# Boobie_LS2074M2G.net
KiCad netlist of a schematic drawn in EAGLE
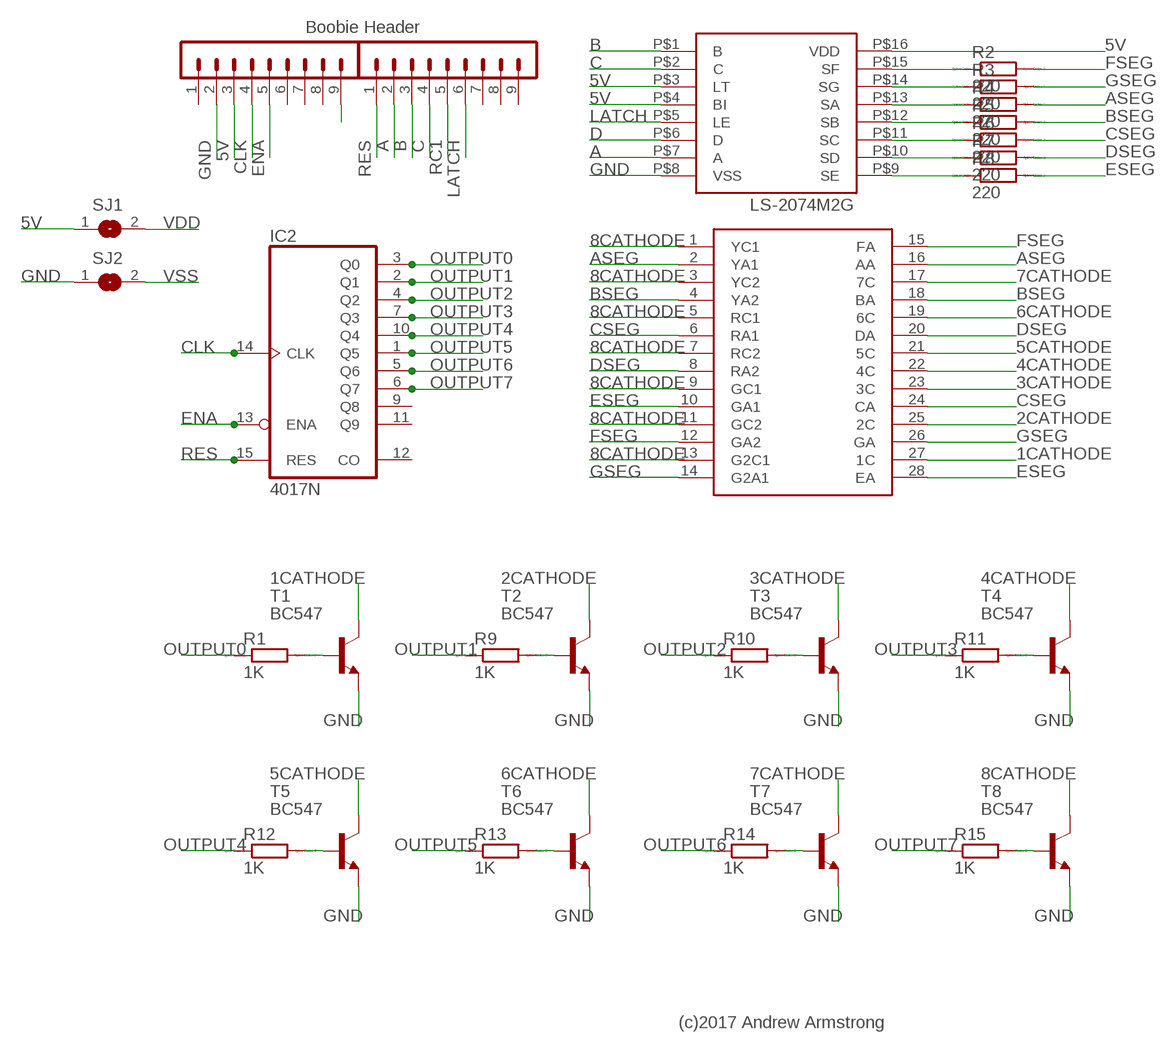
[diagram p0: schematic, sheet 1]

(export (version "E")
  (design (tool "Eeschema 10.0.6"))
  (components
    (comp (ref "IC2")
      (value "4017N")
      (footprint "eagle-import:DIL16")
      (libsource (lib "eagle-import") (part "4017N"))
    )
    (comp (ref "R1")
      (value "1K")
      (footprint "eagle-import:0204_7")
      (libsource (lib "eagle-import") (part "R0204/7"))
    )
    (comp (ref "R2")
      (value "220")
      (footprint "eagle-import:0204_7")
      (libsource (lib "eagle-import") (part "R0204/7"))
    )
    (comp (ref "R3")
      (value "220")
      (footprint "eagle-import:0204_7")
      (libsource (lib "eagle-import") (part "R0204/7"))
    )
    (comp (ref "R4")
      (value "220")
      (footprint "eagle-import:0204_7")
      (libsource (lib "eagle-import") (part "R0204/7"))
    )
    (comp (ref "R5")
      (value "220")
      (footprint "eagle-import:0204_7")
      (libsource (lib "eagle-import") (part "R0204/7"))
    )
    (comp (ref "R6")
      (value "220")
      (footprint "eagle-import:0204_7")
      (libsource (lib "eagle-import") (part "R0204/7"))
    )
    (comp (ref "R7")
      (value "220")
      (footprint "eagle-import:0204_7")
      (libsource (lib "eagle-import") (part "R0204/7"))
    )
    (comp (ref "R8")
      (value "220")
      (footprint "eagle-import:0204_7")
      (libsource (lib "eagle-import") (part "R0204/7"))
    )
    (comp (ref "R9")
      (value "1K")
      (footprint "eagle-import:0204_7")
      (libsource (lib "eagle-import") (part "R0204/7"))
    )
    (comp (ref "R10")
      (value "1K")
      (footprint "eagle-import:0204_7")
      (libsource (lib "eagle-import") (part "R0204/7"))
    )
    (comp (ref "R11")
      (value "1K")
      (footprint "eagle-import:0204_7")
      (libsource (lib "eagle-import") (part "R0204/7"))
    )
    (comp (ref "R12")
      (value "1K")
      (footprint "eagle-import:0204_7")
      (libsource (lib "eagle-import") (part "R0204/7"))
    )
    (comp (ref "R13")
      (value "1K")
      (footprint "eagle-import:0204_7")
      (libsource (lib "eagle-import") (part "R0204/7"))
    )
    (comp (ref "R14")
      (value "1K")
      (footprint "eagle-import:0204_7")
      (libsource (lib "eagle-import") (part "R0204/7"))
    )
    (comp (ref "R15")
      (value "1K")
      (footprint "eagle-import:0204_7")
      (libsource (lib "eagle-import") (part "R0204/7"))
    )
    (comp (ref "SJ1") (value "SJ") (footprint "eagle-import:SJ") (libsource (lib "eagle-import") (part "SJ")))
    (comp (ref "SJ2") (value "SJ") (footprint "eagle-import:SJ") (libsource (lib "eagle-import") (part "SJ")))
    (comp (ref "SV1")
      (value "MA09-1")
      (footprint "eagle-import:MA09-1")
      (libsource (lib "eagle-import") (part "MA09-1"))
    )
    (comp (ref "SV2")
      (value "MA09-1")
      (footprint "eagle-import:MA09-1")
      (libsource (lib "eagle-import") (part "MA09-1"))
    )
    (comp (ref "T1")
      (value "BC547")
      (footprint "eagle-import:TO92")
      (libsource (lib "eagle-import") (part "BC547"))
    )
    (comp (ref "T2")
      (value "BC547")
      (footprint "eagle-import:TO92")
      (libsource (lib "eagle-import") (part "BC547"))
    )
    (comp (ref "T3")
      (value "BC547")
      (footprint "eagle-import:TO92")
      (libsource (lib "eagle-import") (part "BC547"))
    )
    (comp (ref "T4")
      (value "BC547")
      (footprint "eagle-import:TO92")
      (libsource (lib "eagle-import") (part "BC547"))
    )
    (comp (ref "T5")
      (value "BC547")
      (footprint "eagle-import:TO92")
      (libsource (lib "eagle-import") (part "BC547"))
    )
    (comp (ref "T6")
      (value "BC547")
      (footprint "eagle-import:TO92")
      (libsource (lib "eagle-import") (part "BC547"))
    )
    (comp (ref "T7")
      (value "BC547")
      (footprint "eagle-import:TO92")
      (libsource (lib "eagle-import") (part "BC547"))
    )
    (comp (ref "T8")
      (value "BC547")
      (footprint "eagle-import:TO92")
      (libsource (lib "eagle-import") (part "BC547"))
    )
    (comp (ref "U$1")
      (value "LS-2074M2G")
      (footprint "eagle-import:LS-2074M2G")
      (libsource (lib "eagle-import") (part "LS-2074M2G"))
    )
    (comp (ref "U$2")
      (value "MC14511B")
      (footprint "eagle-import:DIL16")
      (libsource (lib "eagle-import") (part "MC14511B"))
    )
  )
  (nets
    (net (code "1") (name "/1CATHODE") (class "Default")
      (node (ref "T1") (pin "3") (pinfunction "C_3") (pintype "passive"))
      (node (ref "U$1") (pin "27") (pinfunction "1C_27") (pintype "bidirectional"))
    )
    (net (code "2") (name "/2CATHODE") (class "Default")
      (node (ref "T2") (pin "3") (pinfunction "C_3") (pintype "passive"))
      (node (ref "U$1") (pin "25") (pinfunction "2C_25") (pintype "bidirectional"))
    )
    (net (code "3") (name "/3CATHODE") (class "Default")
      (node (ref "T3") (pin "3") (pinfunction "C_3") (pintype "passive"))
      (node (ref "U$1") (pin "23") (pinfunction "3C_23") (pintype "bidirectional"))
    )
    (net (code "4") (name "/4CATHODE") (class "Default")
      (node (ref "T4") (pin "3") (pinfunction "C_3") (pintype "passive"))
      (node (ref "U$1") (pin "22") (pinfunction "4C_22") (pintype "bidirectional"))
    )
    (net (code "5") (name "/5CATHODE") (class "Default")
      (node (ref "T5") (pin "3") (pinfunction "C_3") (pintype "passive"))
      (node (ref "U$1") (pin "21") (pinfunction "5C_21") (pintype "bidirectional"))
    )
    (net (code "6") (name "/5V") (class "Default")
      (node (ref "SJ1") (pin "1") (pinfunction "1_1") (pintype "passive"))
      (node (ref "SV2") (pin "3") (pinfunction "3_3") (pintype "passive"))
      (node (ref "U$2") (pin "P$16") (pinfunction "VDD_P$16") (pintype "bidirectional"))
      (node (ref "U$2") (pin "P$3") (pinfunction "LT_P$3") (pintype "bidirectional"))
      (node (ref "U$2") (pin "P$4") (pinfunction "BI_P$4") (pintype "bidirectional"))
    )
    (net (code "7") (name "/6CATHODE") (class "Default")
      (node (ref "T6") (pin "3") (pinfunction "C_3") (pintype "passive"))
      (node (ref "U$1") (pin "19") (pinfunction "6C_19") (pintype "bidirectional"))
    )
    (net (code "8") (name "/7CATHODE") (class "Default")
      (node (ref "T7") (pin "3") (pinfunction "C_3") (pintype "passive"))
      (node (ref "U$1") (pin "17") (pinfunction "7C_17") (pintype "bidirectional"))
    )
    (net (code "9") (name "/8CATHODE") (class "Default")
      (node (ref "T8") (pin "3") (pinfunction "C_3") (pintype "passive"))
      (node (ref "U$1") (pin "1") (pinfunction "YC1_1") (pintype "bidirectional"))
      (node (ref "U$1") (pin "11") (pinfunction "GC2_11") (pintype "bidirectional"))
      (node (ref "U$1") (pin "13") (pinfunction "G2C1_13") (pintype "bidirectional"))
      (node (ref "U$1") (pin "3") (pinfunction "YC2_3") (pintype "bidirectional"))
      (node (ref "U$1") (pin "5") (pinfunction "RC1_5") (pintype "bidirectional"))
      (node (ref "U$1") (pin "7") (pinfunction "RC2_7") (pintype "bidirectional"))
      (node (ref "U$1") (pin "9") (pinfunction "GC1_9") (pintype "bidirectional"))
    )
    (net (code "10") (name "/A") (class "Default")
      (node (ref "SV1") (pin "2") (pinfunction "2_2") (pintype "passive"))
      (node (ref "U$2") (pin "P$7") (pinfunction "A_P$7") (pintype "bidirectional"))
    )
    (net (code "11") (name "/ASEG") (class "Default")
      (node (ref "R4") (pin "2") (pinfunction "2_2") (pintype "passive"))
      (node (ref "U$1") (pin "16") (pinfunction "AA_16") (pintype "bidirectional"))
      (node (ref "U$1") (pin "2") (pinfunction "YA1_2") (pintype "bidirectional"))
    )
    (net (code "12") (name "/B") (class "Default")
      (node (ref "SV1") (pin "3") (pinfunction "3_3") (pintype "passive"))
      (node (ref "U$2") (pin "P$1") (pinfunction "B_P$1") (pintype "bidirectional"))
    )
    (net (code "13") (name "/BSEG") (class "Default")
      (node (ref "R5") (pin "2") (pinfunction "2_2") (pintype "passive"))
      (node (ref "U$1") (pin "18") (pinfunction "BA_18") (pintype "bidirectional"))
      (node (ref "U$1") (pin "4") (pinfunction "YA2_4") (pintype "bidirectional"))
    )
    (net (code "14") (name "/C") (class "Default")
      (node (ref "SV1") (pin "4") (pinfunction "4_4") (pintype "passive"))
      (node (ref "U$2") (pin "P$2") (pinfunction "C_P$2") (pintype "bidirectional"))
    )
    (net (code "15") (name "/CLK") (class "Default")
      (node (ref "IC2") (pin "14") (pinfunction "CLK_14") (pintype "input"))
      (node (ref "SV2") (pin "4") (pinfunction "4_4") (pintype "passive"))
    )
    (net (code "16") (name "/CSEG") (class "Default")
      (node (ref "R6") (pin "2") (pinfunction "2_2") (pintype "passive"))
      (node (ref "U$1") (pin "24") (pinfunction "CA_24") (pintype "bidirectional"))
      (node (ref "U$1") (pin "6") (pinfunction "RA1_6") (pintype "bidirectional"))
    )
    (net (code "17") (name "/D") (class "Default")
      (node (ref "U$2") (pin "P$6") (pinfunction "D_P$6") (pintype "bidirectional"))
    )
    (net (code "18") (name "/DSEG") (class "Default")
      (node (ref "R7") (pin "2") (pinfunction "2_2") (pintype "passive"))
      (node (ref "U$1") (pin "20") (pinfunction "DA_20") (pintype "bidirectional"))
      (node (ref "U$1") (pin "8") (pinfunction "RA2_8") (pintype "bidirectional"))
    )
    (net (code "19") (name "/ENA") (class "Default")
      (node (ref "IC2") (pin "13") (pinfunction "ENA_13") (pintype "input"))
      (node (ref "SV2") (pin "5") (pinfunction "5_5") (pintype "passive"))
    )
    (net (code "20") (name "/ESEG") (class "Default")
      (node (ref "R8") (pin "2") (pinfunction "2_2") (pintype "passive"))
      (node (ref "U$1") (pin "10") (pinfunction "GA1_10") (pintype "bidirectional"))
      (node (ref "U$1") (pin "28") (pinfunction "EA_28") (pintype "bidirectional"))
    )
    (net (code "21") (name "/FSEG") (class "Default")
      (node (ref "R2") (pin "2") (pinfunction "2_2") (pintype "passive"))
      (node (ref "U$1") (pin "12") (pinfunction "GA2_12") (pintype "bidirectional"))
      (node (ref "U$1") (pin "15") (pinfunction "FA_15") (pintype "bidirectional"))
    )
    (net (code "22") (name "/GND") (class "Default")
      (node (ref "SJ2") (pin "1") (pinfunction "1_1") (pintype "passive"))
      (node (ref "SV2") (pin "2") (pinfunction "2_2") (pintype "passive"))
      (node (ref "T1") (pin "1") (pinfunction "E_1") (pintype "passive"))
      (node (ref "T2") (pin "1") (pinfunction "E_1") (pintype "passive"))
      (node (ref "T3") (pin "1") (pinfunction "E_1") (pintype "passive"))
      (node (ref "T4") (pin "1") (pinfunction "E_1") (pintype "passive"))
      (node (ref "T5") (pin "1") (pinfunction "E_1") (pintype "passive"))
      (node (ref "T6") (pin "1") (pinfunction "E_1") (pintype "passive"))
      (node (ref "T7") (pin "1") (pinfunction "E_1") (pintype "passive"))
      (node (ref "T8") (pin "1") (pinfunction "E_1") (pintype "passive"))
      (node (ref "U$2") (pin "P$8") (pinfunction "VSS_P$8") (pintype "bidirectional"))
    )
    (net (code "23") (name "/GSEG") (class "Default")
      (node (ref "R3") (pin "2") (pinfunction "2_2") (pintype "passive"))
      (node (ref "U$1") (pin "14") (pinfunction "G2A1_14") (pintype "bidirectional"))
      (node (ref "U$1") (pin "26") (pinfunction "GA_26") (pintype "bidirectional"))
    )
    (net (code "24") (name "/LATCH") (class "Default")
      (node (ref "SV1") (pin "6") (pinfunction "6_6") (pintype "passive"))
      (node (ref "U$2") (pin "P$5") (pinfunction "LE_P$5") (pintype "bidirectional"))
    )
    (net (code "25") (name "/OUTPUT0") (class "Default")
      (node (ref "IC2") (pin "3") (pinfunction "Q0_3") (pintype "output"))
      (node (ref "R1") (pin "1") (pinfunction "1_1") (pintype "passive"))
    )
    (net (code "26") (name "/OUTPUT1") (class "Default")
      (node (ref "IC2") (pin "2") (pinfunction "Q1_2") (pintype "output"))
      (node (ref "R9") (pin "1") (pinfunction "1_1") (pintype "passive"))
    )
    (net (code "27") (name "/OUTPUT2") (class "Default")
      (node (ref "IC2") (pin "4") (pinfunction "Q2_4") (pintype "output"))
      (node (ref "R10") (pin "1") (pinfunction "1_1") (pintype "passive"))
    )
    (net (code "28") (name "/OUTPUT3") (class "Default")
      (node (ref "IC2") (pin "7") (pinfunction "Q3_7") (pintype "output"))
      (node (ref "R11") (pin "1") (pinfunction "1_1") (pintype "passive"))
    )
    (net (code "29") (name "/OUTPUT4") (class "Default")
      (node (ref "IC2") (pin "10") (pinfunction "Q4_10") (pintype "output"))
      (node (ref "R12") (pin "1") (pinfunction "1_1") (pintype "passive"))
    )
    (net (code "30") (name "/OUTPUT5") (class "Default")
      (node (ref "IC2") (pin "1") (pinfunction "Q5_1") (pintype "output"))
      (node (ref "R13") (pin "1") (pinfunction "1_1") (pintype "passive"))
    )
    (net (code "31") (name "/OUTPUT6") (class "Default")
      (node (ref "IC2") (pin "5") (pinfunction "Q6_5") (pintype "output"))
      (node (ref "R14") (pin "1") (pinfunction "1_1") (pintype "passive"))
    )
    (net (code "32") (name "/OUTPUT7") (class "Default")
      (node (ref "IC2") (pin "6") (pinfunction "Q7_6") (pintype "output"))
      (node (ref "R15") (pin "1") (pinfunction "1_1") (pintype "passive"))
    )
    (net (code "33") (name "/RC1") (class "Default")
      (node (ref "SV1") (pin "5") (pinfunction "5_5") (pintype "passive"))
    )
    (net (code "34") (name "/RES") (class "Default")
      (node (ref "IC2") (pin "15") (pinfunction "RES_15") (pintype "input"))
      (node (ref "SV1") (pin "1") (pinfunction "1_1") (pintype "passive"))
    )
    (net (code "35") (name "/VDD") (class "Default")
      (node (ref "SJ1") (pin "2") (pinfunction "2_2") (pintype "passive"))
    )
    (net (code "36") (name "/VSS") (class "Default")
      (node (ref "SJ2") (pin "2") (pinfunction "2_2") (pintype "passive"))
    )
    (net (code "37") (name "Net-(T1-B)") (class "Default")
      (node (ref "R1") (pin "2") (pinfunction "2_2") (pintype "passive"))
      (node (ref "T1") (pin "2") (pinfunction "B_2") (pintype "passive"))
    )
    (net (code "38") (name "Net-(T2-B)") (class "Default")
      (node (ref "R9") (pin "2") (pinfunction "2_2") (pintype "passive"))
      (node (ref "T2") (pin "2") (pinfunction "B_2") (pintype "passive"))
    )
    (net (code "39") (name "Net-(T3-B)") (class "Default")
      (node (ref "R10") (pin "2") (pinfunction "2_2") (pintype "passive"))
      (node (ref "T3") (pin "2") (pinfunction "B_2") (pintype "passive"))
    )
    (net (code "40") (name "Net-(T4-B)") (class "Default")
      (node (ref "R11") (pin "2") (pinfunction "2_2") (pintype "passive"))
      (node (ref "T4") (pin "2") (pinfunction "B_2") (pintype "passive"))
    )
    (net (code "41") (name "Net-(T5-B)") (class "Default")
      (node (ref "R12") (pin "2") (pinfunction "2_2") (pintype "passive"))
      (node (ref "T5") (pin "2") (pinfunction "B_2") (pintype "passive"))
    )
    (net (code "42") (name "Net-(T6-B)") (class "Default")
      (node (ref "R13") (pin "2") (pinfunction "2_2") (pintype "passive"))
      (node (ref "T6") (pin "2") (pinfunction "B_2") (pintype "passive"))
    )
    (net (code "43") (name "Net-(T7-B)") (class "Default")
      (node (ref "R14") (pin "2") (pinfunction "2_2") (pintype "passive"))
      (node (ref "T7") (pin "2") (pinfunction "B_2") (pintype "passive"))
    )
    (net (code "44") (name "Net-(T8-B)") (class "Default")
      (node (ref "R15") (pin "2") (pinfunction "2_2") (pintype "passive"))
      (node (ref "T8") (pin "2") (pinfunction "B_2") (pintype "passive"))
    )
    (net (code "45") (name "Net-(U$2-SA)") (class "Default")
      (node (ref "R4") (pin "1") (pinfunction "1_1") (pintype "passive"))
      (node (ref "U$2") (pin "P$13") (pinfunction "SA_P$13") (pintype "bidirectional"))
    )
    (net (code "46") (name "Net-(U$2-SB)") (class "Default")
      (node (ref "R5") (pin "1") (pinfunction "1_1") (pintype "passive"))
      (node (ref "U$2") (pin "P$12") (pinfunction "SB_P$12") (pintype "bidirectional"))
    )
    (net (code "47") (name "Net-(U$2-SC)") (class "Default")
      (node (ref "R6") (pin "1") (pinfunction "1_1") (pintype "passive"))
      (node (ref "U$2") (pin "P$11") (pinfunction "SC_P$11") (pintype "bidirectional"))
    )
    (net (code "48") (name "Net-(U$2-SD)") (class "Default")
      (node (ref "R7") (pin "1") (pinfunction "1_1") (pintype "passive"))
      (node (ref "U$2") (pin "P$10") (pinfunction "SD_P$10") (pintype "bidirectional"))
    )
    (net (code "49") (name "Net-(U$2-SE)") (class "Default")
      (node (ref "R8") (pin "1") (pinfunction "1_1") (pintype "passive"))
      (node (ref "U$2") (pin "P$9") (pinfunction "SE_P$9") (pintype "bidirectional"))
    )
    (net (code "50") (name "Net-(U$2-SF)") (class "Default")
      (node (ref "R2") (pin "1") (pinfunction "1_1") (pintype "passive"))
      (node (ref "U$2") (pin "P$15") (pinfunction "SF_P$15") (pintype "bidirectional"))
    )
    (net (code "51") (name "Net-(U$2-SG)") (class "Default")
      (node (ref "R3") (pin "1") (pinfunction "1_1") (pintype "passive"))
      (node (ref "U$2") (pin "P$14") (pinfunction "SG_P$14") (pintype "bidirectional"))
    )
    (net (code "52") (name "unconnected-(IC2A-CO-Pad12)") (class "Default")
      (node (ref "IC2") (pin "12") (pinfunction "CO_12") (pintype "output"))
    )
    (net (code "53") (name "unconnected-(IC2A-Q8-Pad9)") (class "Default")
      (node (ref "IC2") (pin "9") (pinfunction "Q8_9") (pintype "output"))
    )
    (net (code "54") (name "unconnected-(IC2A-Q9-Pad11)") (class "Default")
      (node (ref "IC2") (pin "11") (pinfunction "Q9_11") (pintype "output"))
    )
    (net (code "55") (name "unconnected-(SV1-Pad7)") (class "Default")
      (node (ref "SV1") (pin "7") (pinfunction "7_7") (pintype "passive"))
    )
    (net (code "56") (name "unconnected-(SV1-Pad8)") (class "Default")
      (node (ref "SV1") (pin "8") (pinfunction "8_8") (pintype "passive"))
    )
    (net (code "57") (name "unconnected-(SV1-Pad9)") (class "Default")
      (node (ref "SV1") (pin "9") (pinfunction "9_9") (pintype "passive"))
    )
    (net (code "58") (name "unconnected-(SV2-Pad1)") (class "Default")
      (node (ref "SV2") (pin "1") (pinfunction "1_1") (pintype "passive"))
    )
    (net (code "59") (name "unconnected-(SV2-Pad6)") (class "Default")
      (node (ref "SV2") (pin "6") (pinfunction "6_6") (pintype "passive"))
    )
    (net (code "60") (name "unconnected-(SV2-Pad7)") (class "Default")
      (node (ref "SV2") (pin "7") (pinfunction "7_7") (pintype "passive"))
    )
    (net (code "61") (name "unconnected-(SV2-Pad8)") (class "Default")
      (node (ref "SV2") (pin "8") (pinfunction "8_8") (pintype "passive"))
    )
    (net (code "62") (name "unconnected-(SV2-Pad9)") (class "Default")
      (node (ref "SV2") (pin "9") (pinfunction "9_9") (pintype "passive"))
    )
  )
)
